# schematic_easyeda.net
KiCad netlist of a schematic drawn in EasyEDA
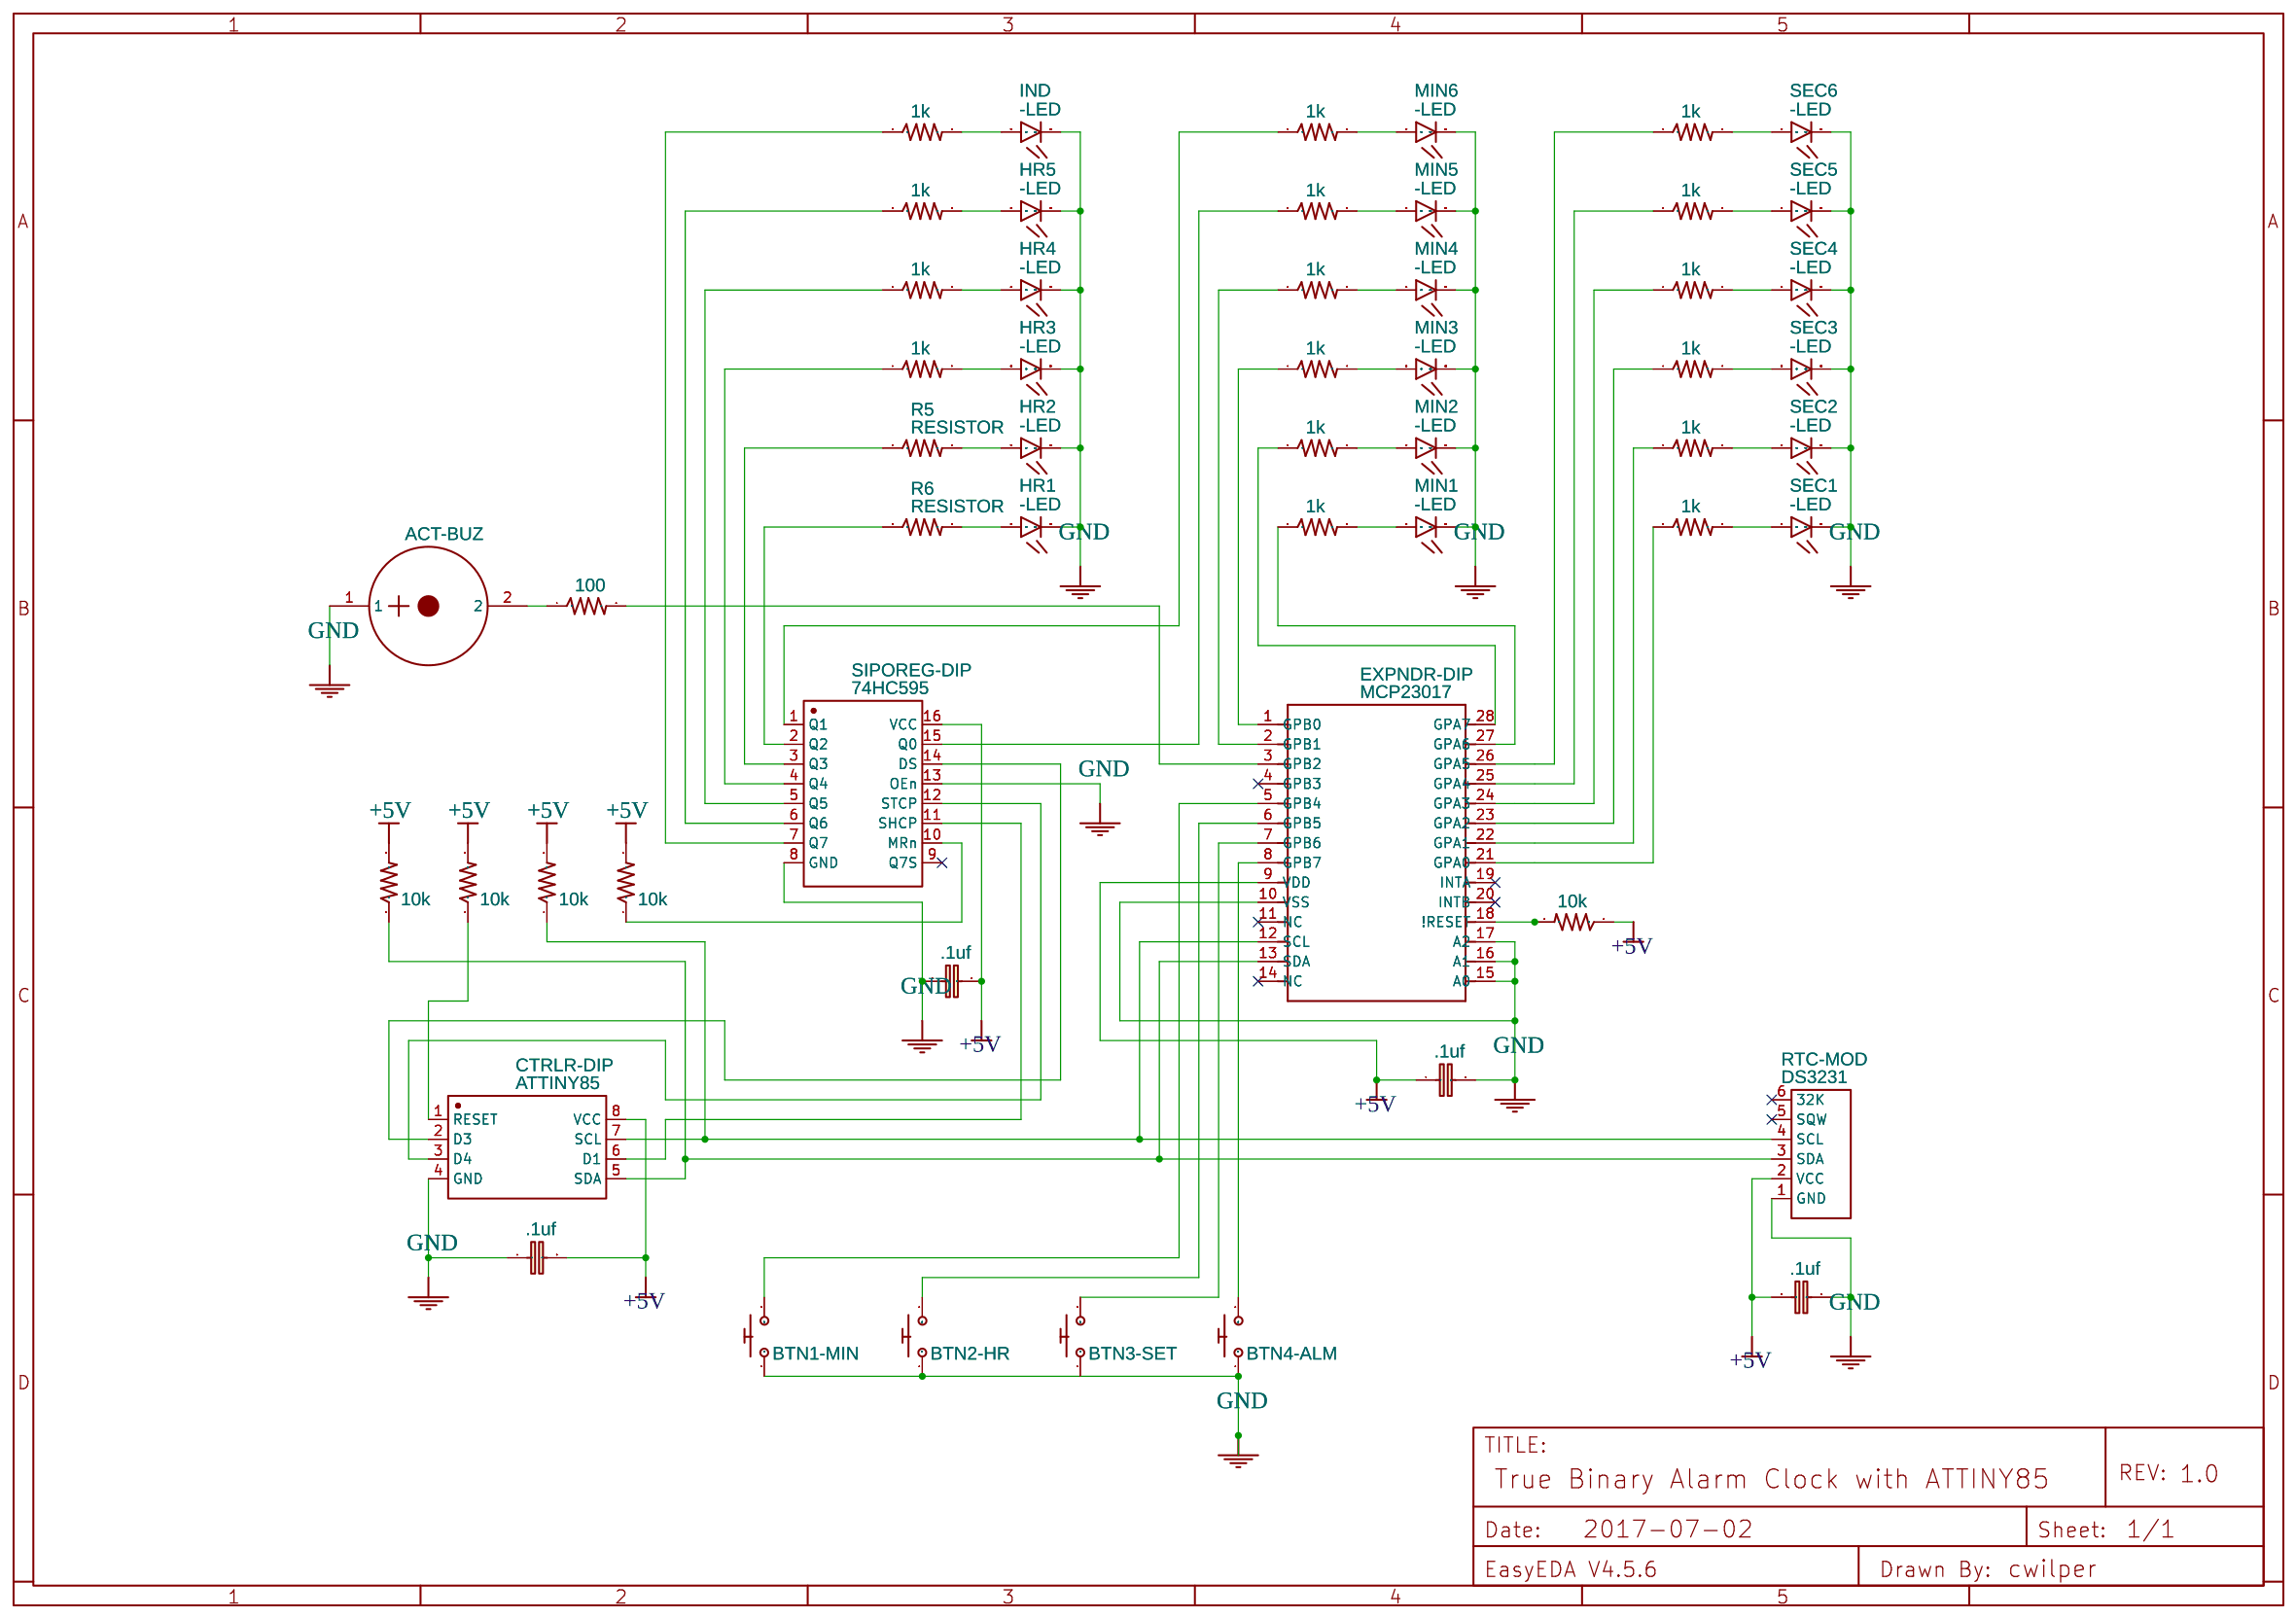
[diagram p0: schematic sheet]

(export (version "E")
  (design (tool "Eeschema 10.0.6"))
  (components
    (comp (ref "BUZ1")
      (value "ACT-BUZ")
      (fields (field (name "BOM_Manufacturer Part") "active buzzer 2300Hz"))
      (libsource (lib "") (part "Unknown_240_330"))
    )
    (comp (ref "C1")
      (value ".1uf")
      (fields (field (name "BOM_Manufacturer Part") "?"))
      (libsource (lib "") (part "Unknown_470_490"))
    )
    (comp (ref "C2")
      (value ".1uf")
      (fields (field (name "BOM_Manufacturer Part") "?"))
      (libsource (lib "") (part "Unknown_270_630"))
    )
    (comp (ref "C3")
      (value ".1uf")
      (fields (field (name "BOM_Manufacturer Part") "?"))
      (libsource (lib "") (part "Unknown_910_650"))
    )
    (comp (ref "C4")
      (value ".1uf")
      (fields (field (name "BOM_Manufacturer Part") "?"))
      (libsource (lib "") (part "Unknown_730_540"))
    )
    (comp (ref "CTRLR-DIP")
      (value "ATTINY85")
      (fields (field (name "BOM_Manufacturer Part") "?"))
      (libsource (lib "") (part "Unknown_270_550"))
    )
    (comp (ref "EXPNDR-DIP")
      (value "MCP23017")
      (fields (field (name "BOM_Manufacturer Part") "MCP23017-E/SO"))
      (libsource (lib "") (part "Unknown_700_430"))
    )
    (comp (ref "HR1")
      (value "-LED")
      (fields (field (name "BOM_Manufacturer Part") "?"))
      (libsource (lib "") (part "Unknown_520_260"))
    )
    (comp (ref "HR2")
      (value "-LED")
      (fields (field (name "BOM_Manufacturer Part") "?"))
      (libsource (lib "") (part "Unknown_520_220"))
    )
    (comp (ref "HR3")
      (value "-LED")
      (fields (field (name "BOM_Manufacturer Part") "?"))
      (libsource (lib "") (part "Unknown_520_180"))
    )
    (comp (ref "HR4")
      (value "-LED")
      (fields (field (name "BOM_Manufacturer Part") "?"))
      (libsource (lib "") (part "Unknown_520_140"))
    )
    (comp (ref "HR5")
      (value "-LED")
      (fields (field (name "BOM_Manufacturer Part") "?"))
      (libsource (lib "") (part "Unknown_520_100"))
    )
    (comp (ref "IND")
      (value "-LED")
      (fields (field (name "BOM_Manufacturer Part") "?"))
      (libsource (lib "") (part "Unknown_520_60"))
    )
    (comp (ref "MIN1")
      (value "-LED")
      (fields (field (name "BOM_Manufacturer Part") "?"))
      (libsource (lib "") (part "Unknown_720_260"))
    )
    (comp (ref "MIN2")
      (value "-LED")
      (fields (field (name "BOM_Manufacturer Part") "?"))
      (libsource (lib "") (part "Unknown_720_220"))
    )
    (comp (ref "MIN3")
      (value "-LED")
      (fields (field (name "BOM_Manufacturer Part") "?"))
      (libsource (lib "") (part "Unknown_720_180"))
    )
    (comp (ref "MIN4")
      (value "-LED")
      (fields (field (name "BOM_Manufacturer Part") "?"))
      (libsource (lib "") (part "Unknown_720_140"))
    )
    (comp (ref "MIN5")
      (value "-LED")
      (fields (field (name "BOM_Manufacturer Part") "?"))
      (libsource (lib "") (part "Unknown_720_100"))
    )
    (comp (ref "MIN6")
      (value "-LED")
      (fields (field (name "BOM_Manufacturer Part") "?"))
      (libsource (lib "") (part "Unknown_720_60"))
    )
    (comp (ref "R")
      (value "100")
      (fields (field (name "BOM_Manufacturer Part") "?"))
      (libsource (lib "") (part "Unknown_290_300"))
    )
    (comp (ref "R1")
      (value "1k")
      (fields (field (name "BOM_Manufacturer Part") "?"))
      (libsource (lib "") (part "Unknown_460_60"))
    )
    (comp (ref "R2")
      (value "1k")
      (fields (field (name "BOM_Manufacturer Part") "?"))
      (libsource (lib "") (part "Unknown_460_100"))
    )
    (comp (ref "R3")
      (value "1k")
      (fields (field (name "BOM_Manufacturer Part") "?"))
      (libsource (lib "") (part "Unknown_460_140"))
    )
    (comp (ref "R4")
      (value "1k")
      (fields (field (name "BOM_Manufacturer Part") "?"))
      (libsource (lib "") (part "Unknown_460_180"))
    )
    (comp (ref "R5")
      (value "RESISTOR")
      (fields (field (name "BOM_Manufacturer Part") "?"))
      (libsource (lib "") (part "Unknown_460_220"))
    )
    (comp (ref "R6")
      (value "RESISTOR")
      (fields (field (name "BOM_Manufacturer Part") "?"))
      (libsource (lib "") (part "Unknown_460_260"))
    )
    (comp (ref "R7")
      (value "1k")
      (fields (field (name "BOM_Manufacturer Part") "?"))
      (libsource (lib "") (part "Unknown_660_60"))
    )
    (comp (ref "R8")
      (value "1k")
      (fields (field (name "BOM_Manufacturer Part") "?"))
      (libsource (lib "") (part "Unknown_660_100"))
    )
    (comp (ref "R9")
      (value "1k")
      (fields (field (name "BOM_Manufacturer Part") "?"))
      (libsource (lib "") (part "Unknown_660_140"))
    )
    (comp (ref "R10")
      (value "1k")
      (fields (field (name "BOM_Manufacturer Part") "?"))
      (libsource (lib "") (part "Unknown_660_180"))
    )
    (comp (ref "R11")
      (value "1k")
      (fields (field (name "BOM_Manufacturer Part") "?"))
      (libsource (lib "") (part "Unknown_660_220"))
    )
    (comp (ref "R12")
      (value "1k")
      (fields (field (name "BOM_Manufacturer Part") "?"))
      (libsource (lib "") (part "Unknown_660_260"))
    )
    (comp (ref "R13")
      (value "1k")
      (fields (field (name "BOM_Manufacturer Part") "?"))
      (libsource (lib "") (part "Unknown_850_60"))
    )
    (comp (ref "R14")
      (value "1k")
      (fields (field (name "BOM_Manufacturer Part") "?"))
      (libsource (lib "") (part "Unknown_850_100"))
    )
    (comp (ref "R15")
      (value "1k")
      (fields (field (name "BOM_Manufacturer Part") "?"))
      (libsource (lib "") (part "Unknown_850_140"))
    )
    (comp (ref "R16")
      (value "1k")
      (fields (field (name "BOM_Manufacturer Part") "?"))
      (libsource (lib "") (part "Unknown_850_180"))
    )
    (comp (ref "R17")
      (value "1k")
      (fields (field (name "BOM_Manufacturer Part") "?"))
      (libsource (lib "") (part "Unknown_850_220"))
    )
    (comp (ref "R18")
      (value "1k")
      (fields (field (name "BOM_Manufacturer Part") "?"))
      (libsource (lib "") (part "Unknown_850_260"))
    )
    (comp (ref "R19")
      (value "10k")
      (fields (field (name "BOM_Manufacturer Part") "?"))
      (libsource (lib "") (part "Unknown_270_440"))
    )
    (comp (ref "R20")
      (value "10k")
      (fields (field (name "BOM_Manufacturer Part") "?"))
      (libsource (lib "") (part "Unknown_190_440"))
    )
    (comp (ref "R21")
      (value "10k")
      (fields (field (name "BOM_Manufacturer Part") "?"))
      (libsource (lib "") (part "Unknown_790_460"))
    )
    (comp (ref "R22")
      (value "10k")
      (fields (field (name "BOM_Manufacturer Part") "?"))
      (libsource (lib "") (part "Unknown_230_440"))
    )
    (comp (ref "R23")
      (value "10k")
      (fields (field (name "BOM_Manufacturer Part") "?"))
      (libsource (lib "") (part "Unknown_310_440"))
    )
    (comp (ref "RTC-MOD")
      (value "DS3231")
      (fields (field (name "BOM_Manufacturer Part") "?"))
      (libsource (lib "") (part "Unknown_910_590"))
    )
    (comp (ref "SEC1")
      (value "-LED")
      (fields (field (name "BOM_Manufacturer Part") "?"))
      (libsource (lib "") (part "Unknown_910_260"))
    )
    (comp (ref "SEC2")
      (value "-LED")
      (fields (field (name "BOM_Manufacturer Part") "?"))
      (libsource (lib "") (part "Unknown_910_220"))
    )
    (comp (ref "SEC3")
      (value "-LED")
      (fields (field (name "BOM_Manufacturer Part") "?"))
      (libsource (lib "") (part "Unknown_910_180"))
    )
    (comp (ref "SEC4")
      (value "-LED")
      (fields (field (name "BOM_Manufacturer Part") "?"))
      (libsource (lib "") (part "Unknown_910_140"))
    )
    (comp (ref "SEC5")
      (value "-LED")
      (fields (field (name "BOM_Manufacturer Part") "?"))
      (libsource (lib "") (part "Unknown_910_100"))
    )
    (comp (ref "SEC6")
      (value "-LED")
      (fields (field (name "BOM_Manufacturer Part") "?"))
      (libsource (lib "") (part "Unknown_910_60"))
    )
    (comp (ref "SIPOREG-DIP")
      (value "74HC595")
      (fields (field (name "BOM_Manufacturer Part") "?"))
      (libsource (lib "") (part "74HC595EE"))
    )
    (comp (ref "SW-1SWITCH")
      (value "BTN4-ALM")
      (fields (field (name "BOM_Manufacturer Part") "?"))
      (libsource (lib "") (part "Unknown_620_670"))
    )
    (comp (ref "SW-2SWITCH")
      (value "BTN3-SET")
      (fields (field (name "BOM_Manufacturer Part") "?"))
      (libsource (lib "") (part "Unknown_540_670"))
    )
    (comp (ref "SW-3SWITCH")
      (value "BTN2-HR")
      (fields (field (name "BOM_Manufacturer Part") "?"))
      (libsource (lib "") (part "Unknown_460_670"))
    )
    (comp (ref "SW-4SWITCH")
      (value "BTN1-MIN")
      (fields (field (name "BOM_Manufacturer Part") "?"))
      (libsource (lib "") (part "Unknown_380_670"))
    )
  )
  (nets
    (net (code "1") (name "+5V") (class "Default")
      (node (ref "C1") (pin "1") (pinfunction "1_1") (pintype "unspecified"))
      (node (ref "C2") (pin "2") (pinfunction "2_2") (pintype "unspecified"))
      (node (ref "C3") (pin "1") (pinfunction "1_1") (pintype "unspecified"))
      (node (ref "C4") (pin "1") (pinfunction "1_1") (pintype "unspecified"))
      (node (ref "CTRLR-DIP") (pin "8") (pinfunction "VCC_8") (pintype "unspecified"))
      (node (ref "EXPNDR-DIP") (pin "9") (pinfunction "VDD_9") (pintype "unspecified"))
      (node (ref "R19") (pin "2") (pinfunction "2_2") (pintype "unspecified"))
      (node (ref "R20") (pin "2") (pinfunction "2_2") (pintype "unspecified"))
      (node (ref "R21") (pin "1") (pinfunction "1_1") (pintype "unspecified"))
      (node (ref "R22") (pin "2") (pinfunction "2_2") (pintype "unspecified"))
      (node (ref "R23") (pin "2") (pinfunction "2_2") (pintype "unspecified"))
      (node (ref "RTC-MOD") (pin "2") (pinfunction "VCC_2") (pintype "input"))
      (node (ref "SIPOREG-DIP") (pin "16") (pinfunction "VCC_16") (pintype "unspecified"))
    )
    (net (code "2") (name "GND") (class "Default")
      (node (ref "BUZ1") (pin "1") (pinfunction "1_1") (pintype "unspecified"))
      (node (ref "C1") (pin "2") (pinfunction "2_2") (pintype "unspecified"))
      (node (ref "C2") (pin "1") (pinfunction "1_1") (pintype "unspecified"))
      (node (ref "C3") (pin "2") (pinfunction "2_2") (pintype "unspecified"))
      (node (ref "C4") (pin "2") (pinfunction "2_2") (pintype "unspecified"))
      (node (ref "CTRLR-DIP") (pin "4") (pinfunction "GND_4") (pintype "unspecified"))
      (node (ref "EXPNDR-DIP") (pin "10") (pinfunction "VSS_10") (pintype "unspecified"))
      (node (ref "EXPNDR-DIP") (pin "15") (pinfunction "A0_15") (pintype "unspecified"))
      (node (ref "EXPNDR-DIP") (pin "16") (pinfunction "A1_16") (pintype "unspecified"))
      (node (ref "EXPNDR-DIP") (pin "17") (pinfunction "A2_17") (pintype "unspecified"))
      (node (ref "HR1") (pin "CATHODE") (pinfunction "CATHODE_CATHODE") (pintype "unspecified"))
      (node (ref "HR2") (pin "CATHODE") (pinfunction "CATHODE_CATHODE") (pintype "unspecified"))
      (node (ref "HR3") (pin "CATHODE") (pinfunction "CATHODE_CATHODE") (pintype "unspecified"))
      (node (ref "HR4") (pin "CATHODE") (pinfunction "CATHODE_CATHODE") (pintype "unspecified"))
      (node (ref "HR5") (pin "CATHODE") (pinfunction "CATHODE_CATHODE") (pintype "unspecified"))
      (node (ref "IND") (pin "CATHODE") (pinfunction "CATHODE_CATHODE") (pintype "unspecified"))
      (node (ref "MIN1") (pin "CATHODE") (pinfunction "CATHODE_CATHODE") (pintype "unspecified"))
      (node (ref "MIN2") (pin "CATHODE") (pinfunction "CATHODE_CATHODE") (pintype "unspecified"))
      (node (ref "MIN3") (pin "CATHODE") (pinfunction "CATHODE_CATHODE") (pintype "unspecified"))
      (node (ref "MIN4") (pin "CATHODE") (pinfunction "CATHODE_CATHODE") (pintype "unspecified"))
      (node (ref "MIN5") (pin "CATHODE") (pinfunction "CATHODE_CATHODE") (pintype "unspecified"))
      (node (ref "MIN6") (pin "CATHODE") (pinfunction "CATHODE_CATHODE") (pintype "unspecified"))
      (node (ref "RTC-MOD") (pin "1") (pinfunction "GND_1") (pintype "input"))
      (node (ref "SEC1") (pin "CATHODE") (pinfunction "CATHODE_CATHODE") (pintype "unspecified"))
      (node (ref "SEC2") (pin "CATHODE") (pinfunction "CATHODE_CATHODE") (pintype "unspecified"))
      (node (ref "SEC3") (pin "CATHODE") (pinfunction "CATHODE_CATHODE") (pintype "unspecified"))
      (node (ref "SEC4") (pin "CATHODE") (pinfunction "CATHODE_CATHODE") (pintype "unspecified"))
      (node (ref "SEC5") (pin "CATHODE") (pinfunction "CATHODE_CATHODE") (pintype "unspecified"))
      (node (ref "SEC6") (pin "CATHODE") (pinfunction "CATHODE_CATHODE") (pintype "unspecified"))
      (node (ref "SIPOREG-DIP") (pin "13") (pinfunction "OEn_13") (pintype "unspecified"))
      (node (ref "SIPOREG-DIP") (pin "8") (pinfunction "GND_8") (pintype "unspecified"))
      (node (ref "SW-1SWITCH") (pin "1") (pinfunction "P$1_1") (pintype "unspecified"))
      (node (ref "SW-2SWITCH") (pin "1") (pinfunction "P$1_1") (pintype "unspecified"))
      (node (ref "SW-3SWITCH") (pin "1") (pinfunction "P$1_1") (pintype "unspecified"))
      (node (ref "SW-4SWITCH") (pin "1") (pinfunction "P$1_1") (pintype "unspecified"))
    )
    (net (code "3") (name "Net-(BUZ1-Pad2)") (class "Default")
      (node (ref "BUZ1") (pin "2") (pinfunction "2_2") (pintype "unspecified"))
      (node (ref "R") (pin "1") (pinfunction "1_1") (pintype "unspecified"))
    )
    (net (code "4") (name "Net-(CTRLR-DIP-D1)") (class "Default")
      (node (ref "CTRLR-DIP") (pin "6") (pinfunction "D1_6") (pintype "unspecified"))
      (node (ref "SIPOREG-DIP") (pin "11") (pinfunction "SHCP_11") (pintype "unspecified"))
    )
    (net (code "5") (name "Net-(CTRLR-DIP-D3)") (class "Default")
      (node (ref "CTRLR-DIP") (pin "2") (pinfunction "D3_2") (pintype "unspecified"))
      (node (ref "SIPOREG-DIP") (pin "14") (pinfunction "DS_14") (pintype "unspecified"))
    )
    (net (code "6") (name "Net-(CTRLR-DIP-D4)") (class "Default")
      (node (ref "CTRLR-DIP") (pin "3") (pinfunction "D4_3") (pintype "unspecified"))
      (node (ref "SIPOREG-DIP") (pin "12") (pinfunction "STCP_12") (pintype "unspecified"))
    )
    (net (code "7") (name "Net-(CTRLR-DIP-RESET)") (class "Default")
      (node (ref "CTRLR-DIP") (pin "1") (pinfunction "RESET_1") (pintype "unspecified"))
      (node (ref "R22") (pin "1") (pinfunction "1_1") (pintype "unspecified"))
    )
    (net (code "8") (name "Net-(CTRLR-DIP-SCL)") (class "Default")
      (node (ref "CTRLR-DIP") (pin "7") (pinfunction "SCL_7") (pintype "unspecified"))
      (node (ref "EXPNDR-DIP") (pin "12") (pinfunction "SCL_12") (pintype "unspecified"))
      (node (ref "R19") (pin "1") (pinfunction "1_1") (pintype "unspecified"))
      (node (ref "RTC-MOD") (pin "4") (pinfunction "SCL_4") (pintype "input"))
    )
    (net (code "9") (name "Net-(CTRLR-DIP-SDA)") (class "Default")
      (node (ref "CTRLR-DIP") (pin "5") (pinfunction "SDA_5") (pintype "unspecified"))
      (node (ref "EXPNDR-DIP") (pin "13") (pinfunction "SDA_13") (pintype "unspecified"))
      (node (ref "R20") (pin "1") (pinfunction "1_1") (pintype "unspecified"))
      (node (ref "RTC-MOD") (pin "3") (pinfunction "SDA_3") (pintype "input"))
    )
    (net (code "10") (name "Net-(EXPNDR-DIP-!RESET)") (class "Default")
      (node (ref "EXPNDR-DIP") (pin "18") (pinfunction "!RESET_18") (pintype "unspecified"))
      (node (ref "R21") (pin "2") (pinfunction "2_2") (pintype "unspecified"))
    )
    (net (code "11") (name "Net-(EXPNDR-DIP-GPA0)") (class "Default")
      (node (ref "EXPNDR-DIP") (pin "21") (pinfunction "GPA0_21") (pintype "unspecified"))
      (node (ref "R18") (pin "1") (pinfunction "1_1") (pintype "unspecified"))
    )
    (net (code "12") (name "Net-(EXPNDR-DIP-GPA1)") (class "Default")
      (node (ref "EXPNDR-DIP") (pin "22") (pinfunction "GPA1_22") (pintype "unspecified"))
      (node (ref "R17") (pin "1") (pinfunction "1_1") (pintype "unspecified"))
    )
    (net (code "13") (name "Net-(EXPNDR-DIP-GPA2)") (class "Default")
      (node (ref "EXPNDR-DIP") (pin "23") (pinfunction "GPA2_23") (pintype "unspecified"))
      (node (ref "R16") (pin "1") (pinfunction "1_1") (pintype "unspecified"))
    )
    (net (code "14") (name "Net-(EXPNDR-DIP-GPA3)") (class "Default")
      (node (ref "EXPNDR-DIP") (pin "24") (pinfunction "GPA3_24") (pintype "unspecified"))
      (node (ref "R15") (pin "1") (pinfunction "1_1") (pintype "unspecified"))
    )
    (net (code "15") (name "Net-(EXPNDR-DIP-GPA4)") (class "Default")
      (node (ref "EXPNDR-DIP") (pin "25") (pinfunction "GPA4_25") (pintype "unspecified"))
      (node (ref "R14") (pin "1") (pinfunction "1_1") (pintype "unspecified"))
    )
    (net (code "16") (name "Net-(EXPNDR-DIP-GPA5)") (class "Default")
      (node (ref "EXPNDR-DIP") (pin "26") (pinfunction "GPA5_26") (pintype "unspecified"))
      (node (ref "R13") (pin "1") (pinfunction "1_1") (pintype "unspecified"))
    )
    (net (code "17") (name "Net-(EXPNDR-DIP-GPA6)") (class "Default")
      (node (ref "EXPNDR-DIP") (pin "27") (pinfunction "GPA6_27") (pintype "unspecified"))
      (node (ref "R12") (pin "1") (pinfunction "1_1") (pintype "unspecified"))
    )
    (net (code "18") (name "Net-(EXPNDR-DIP-GPA7)") (class "Default")
      (node (ref "EXPNDR-DIP") (pin "28") (pinfunction "GPA7_28") (pintype "unspecified"))
      (node (ref "R11") (pin "1") (pinfunction "1_1") (pintype "unspecified"))
    )
    (net (code "19") (name "Net-(EXPNDR-DIP-GPB0)") (class "Default")
      (node (ref "EXPNDR-DIP") (pin "1") (pinfunction "GPB0_1") (pintype "unspecified"))
      (node (ref "R10") (pin "1") (pinfunction "1_1") (pintype "unspecified"))
    )
    (net (code "20") (name "Net-(EXPNDR-DIP-GPB1)") (class "Default")
      (node (ref "EXPNDR-DIP") (pin "2") (pinfunction "GPB1_2") (pintype "unspecified"))
      (node (ref "R9") (pin "1") (pinfunction "1_1") (pintype "unspecified"))
    )
    (net (code "21") (name "Net-(EXPNDR-DIP-GPB2)") (class "Default")
      (node (ref "EXPNDR-DIP") (pin "3") (pinfunction "GPB2_3") (pintype "unspecified"))
      (node (ref "R") (pin "2") (pinfunction "2_2") (pintype "unspecified"))
    )
    (net (code "22") (name "Net-(EXPNDR-DIP-GPB4)") (class "Default")
      (node (ref "EXPNDR-DIP") (pin "5") (pinfunction "GPB4_5") (pintype "unspecified"))
      (node (ref "SW-4SWITCH") (pin "2") (pinfunction "P$2_2") (pintype "unspecified"))
    )
    (net (code "23") (name "Net-(EXPNDR-DIP-GPB5)") (class "Default")
      (node (ref "EXPNDR-DIP") (pin "6") (pinfunction "GPB5_6") (pintype "unspecified"))
      (node (ref "SW-3SWITCH") (pin "2") (pinfunction "P$2_2") (pintype "unspecified"))
    )
    (net (code "24") (name "Net-(EXPNDR-DIP-GPB6)") (class "Default")
      (node (ref "EXPNDR-DIP") (pin "7") (pinfunction "GPB6_7") (pintype "unspecified"))
      (node (ref "SW-2SWITCH") (pin "2") (pinfunction "P$2_2") (pintype "unspecified"))
    )
    (net (code "25") (name "Net-(EXPNDR-DIP-GPB7)") (class "Default")
      (node (ref "EXPNDR-DIP") (pin "8") (pinfunction "GPB7_8") (pintype "unspecified"))
      (node (ref "SW-1SWITCH") (pin "2") (pinfunction "P$2_2") (pintype "unspecified"))
    )
    (net (code "26") (name "Net-(HR1-PadANODE)") (class "Default")
      (node (ref "HR1") (pin "ANODE") (pinfunction "ANODE_ANODE") (pintype "unspecified"))
      (node (ref "R6") (pin "2") (pinfunction "2_2") (pintype "unspecified"))
    )
    (net (code "27") (name "Net-(HR2-PadANODE)") (class "Default")
      (node (ref "HR2") (pin "ANODE") (pinfunction "ANODE_ANODE") (pintype "unspecified"))
      (node (ref "R5") (pin "2") (pinfunction "2_2") (pintype "unspecified"))
    )
    (net (code "28") (name "Net-(HR3-PadANODE)") (class "Default")
      (node (ref "HR3") (pin "ANODE") (pinfunction "ANODE_ANODE") (pintype "unspecified"))
      (node (ref "R4") (pin "2") (pinfunction "2_2") (pintype "unspecified"))
    )
    (net (code "29") (name "Net-(HR4-PadANODE)") (class "Default")
      (node (ref "HR4") (pin "ANODE") (pinfunction "ANODE_ANODE") (pintype "unspecified"))
      (node (ref "R3") (pin "2") (pinfunction "2_2") (pintype "unspecified"))
    )
    (net (code "30") (name "Net-(HR5-PadANODE)") (class "Default")
      (node (ref "HR5") (pin "ANODE") (pinfunction "ANODE_ANODE") (pintype "unspecified"))
      (node (ref "R2") (pin "2") (pinfunction "2_2") (pintype "unspecified"))
    )
    (net (code "31") (name "Net-(IND-PadANODE)") (class "Default")
      (node (ref "IND") (pin "ANODE") (pinfunction "ANODE_ANODE") (pintype "unspecified"))
      (node (ref "R1") (pin "2") (pinfunction "2_2") (pintype "unspecified"))
    )
    (net (code "32") (name "Net-(MIN1-PadANODE)") (class "Default")
      (node (ref "MIN1") (pin "ANODE") (pinfunction "ANODE_ANODE") (pintype "unspecified"))
      (node (ref "R12") (pin "2") (pinfunction "2_2") (pintype "unspecified"))
    )
    (net (code "33") (name "Net-(MIN2-PadANODE)") (class "Default")
      (node (ref "MIN2") (pin "ANODE") (pinfunction "ANODE_ANODE") (pintype "unspecified"))
      (node (ref "R11") (pin "2") (pinfunction "2_2") (pintype "unspecified"))
    )
    (net (code "34") (name "Net-(MIN3-PadANODE)") (class "Default")
      (node (ref "MIN3") (pin "ANODE") (pinfunction "ANODE_ANODE") (pintype "unspecified"))
      (node (ref "R10") (pin "2") (pinfunction "2_2") (pintype "unspecified"))
    )
    (net (code "35") (name "Net-(MIN4-PadANODE)") (class "Default")
      (node (ref "MIN4") (pin "ANODE") (pinfunction "ANODE_ANODE") (pintype "unspecified"))
      (node (ref "R9") (pin "2") (pinfunction "2_2") (pintype "unspecified"))
    )
    (net (code "36") (name "Net-(MIN5-PadANODE)") (class "Default")
      (node (ref "MIN5") (pin "ANODE") (pinfunction "ANODE_ANODE") (pintype "unspecified"))
      (node (ref "R8") (pin "2") (pinfunction "2_2") (pintype "unspecified"))
    )
    (net (code "37") (name "Net-(MIN6-PadANODE)") (class "Default")
      (node (ref "MIN6") (pin "ANODE") (pinfunction "ANODE_ANODE") (pintype "unspecified"))
      (node (ref "R7") (pin "2") (pinfunction "2_2") (pintype "unspecified"))
    )
    (net (code "38") (name "Net-(R13-Pad2)") (class "Default")
      (node (ref "R13") (pin "2") (pinfunction "2_2") (pintype "unspecified"))
      (node (ref "SEC6") (pin "ANODE") (pinfunction "ANODE_ANODE") (pintype "unspecified"))
    )
    (net (code "39") (name "Net-(R14-Pad2)") (class "Default")
      (node (ref "R14") (pin "2") (pinfunction "2_2") (pintype "unspecified"))
      (node (ref "SEC5") (pin "ANODE") (pinfunction "ANODE_ANODE") (pintype "unspecified"))
    )
    (net (code "40") (name "Net-(R15-Pad2)") (class "Default")
      (node (ref "R15") (pin "2") (pinfunction "2_2") (pintype "unspecified"))
      (node (ref "SEC4") (pin "ANODE") (pinfunction "ANODE_ANODE") (pintype "unspecified"))
    )
    (net (code "41") (name "Net-(R16-Pad2)") (class "Default")
      (node (ref "R16") (pin "2") (pinfunction "2_2") (pintype "unspecified"))
      (node (ref "SEC3") (pin "ANODE") (pinfunction "ANODE_ANODE") (pintype "unspecified"))
    )
    (net (code "42") (name "Net-(R17-Pad2)") (class "Default")
      (node (ref "R17") (pin "2") (pinfunction "2_2") (pintype "unspecified"))
      (node (ref "SEC2") (pin "ANODE") (pinfunction "ANODE_ANODE") (pintype "unspecified"))
    )
    (net (code "43") (name "Net-(R18-Pad2)") (class "Default")
      (node (ref "R18") (pin "2") (pinfunction "2_2") (pintype "unspecified"))
      (node (ref "SEC1") (pin "ANODE") (pinfunction "ANODE_ANODE") (pintype "unspecified"))
    )
    (net (code "44") (name "Net-(SIPOREG-DIP-MRn)") (class "Default")
      (node (ref "R23") (pin "1") (pinfunction "1_1") (pintype "unspecified"))
      (node (ref "SIPOREG-DIP") (pin "10") (pinfunction "MRn_10") (pintype "unspecified"))
    )
    (net (code "45") (name "Net-(SIPOREG-DIP-Q0)") (class "Default")
      (node (ref "R8") (pin "1") (pinfunction "1_1") (pintype "unspecified"))
      (node (ref "SIPOREG-DIP") (pin "15") (pinfunction "Q0_15") (pintype "unspecified"))
    )
    (net (code "46") (name "Net-(SIPOREG-DIP-Q1)") (class "Default")
      (node (ref "R7") (pin "1") (pinfunction "1_1") (pintype "unspecified"))
      (node (ref "SIPOREG-DIP") (pin "1") (pinfunction "Q1_1") (pintype "unspecified"))
    )
    (net (code "47") (name "Net-(SIPOREG-DIP-Q2)") (class "Default")
      (node (ref "R6") (pin "1") (pinfunction "1_1") (pintype "unspecified"))
      (node (ref "SIPOREG-DIP") (pin "2") (pinfunction "Q2_2") (pintype "unspecified"))
    )
    (net (code "48") (name "Net-(SIPOREG-DIP-Q3)") (class "Default")
      (node (ref "R5") (pin "1") (pinfunction "1_1") (pintype "unspecified"))
      (node (ref "SIPOREG-DIP") (pin "3") (pinfunction "Q3_3") (pintype "unspecified"))
    )
    (net (code "49") (name "Net-(SIPOREG-DIP-Q4)") (class "Default")
      (node (ref "R4") (pin "1") (pinfunction "1_1") (pintype "unspecified"))
      (node (ref "SIPOREG-DIP") (pin "4") (pinfunction "Q4_4") (pintype "unspecified"))
    )
    (net (code "50") (name "Net-(SIPOREG-DIP-Q5)") (class "Default")
      (node (ref "R3") (pin "1") (pinfunction "1_1") (pintype "unspecified"))
      (node (ref "SIPOREG-DIP") (pin "5") (pinfunction "Q5_5") (pintype "unspecified"))
    )
    (net (code "51") (name "Net-(SIPOREG-DIP-Q6)") (class "Default")
      (node (ref "R2") (pin "1") (pinfunction "1_1") (pintype "unspecified"))
      (node (ref "SIPOREG-DIP") (pin "6") (pinfunction "Q6_6") (pintype "unspecified"))
    )
    (net (code "52") (name "Net-(SIPOREG-DIP-Q7)") (class "Default")
      (node (ref "R1") (pin "1") (pinfunction "1_1") (pintype "unspecified"))
      (node (ref "SIPOREG-DIP") (pin "7") (pinfunction "Q7_7") (pintype "unspecified"))
    )
    (net (code "53") (name "unconnected-(EXPNDR-DIP-GPB3-Pad4)") (class "Default")
      (node (ref "EXPNDR-DIP") (pin "4") (pinfunction "GPB3_4") (pintype "unspecified+no_connect"))
    )
    (net (code "54") (name "unconnected-(EXPNDR-DIP-INTA-Pad19)") (class "Default")
      (node (ref "EXPNDR-DIP") (pin "19") (pinfunction "INTA_19") (pintype "unspecified+no_connect"))
    )
    (net (code "55") (name "unconnected-(EXPNDR-DIP-INTB-Pad20)") (class "Default")
      (node (ref "EXPNDR-DIP") (pin "20") (pinfunction "INTB_20") (pintype "unspecified+no_connect"))
    )
    (net (code "56") (name "unconnected-(EXPNDR-DIP-NC-Pad11)") (class "Default")
      (node (ref "EXPNDR-DIP") (pin "11") (pinfunction "NC_11") (pintype "unspecified+no_connect"))
    )
    (net (code "57") (name "unconnected-(EXPNDR-DIP-NC-Pad14)") (class "Default")
      (node (ref "EXPNDR-DIP") (pin "14") (pinfunction "NC_14") (pintype "unspecified+no_connect"))
    )
    (net (code "58") (name "unconnected-(RTC-MOD-32K-Pad6)") (class "Default")
      (node (ref "RTC-MOD") (pin "6") (pinfunction "32K_6") (pintype "input+no_connect"))
    )
    (net (code "59") (name "unconnected-(RTC-MOD-SQW-Pad5)") (class "Default")
      (node (ref "RTC-MOD") (pin "5") (pinfunction "SQW_5") (pintype "input+no_connect"))
    )
    (net (code "60") (name "unconnected-(SIPOREG-DIP-Q7S-Pad9)") (class "Default")
      (node (ref "SIPOREG-DIP") (pin "9") (pinfunction "Q7S_9") (pintype "unspecified+no_connect"))
    )
  )
)
